# sparkfantutorial.net
KiCad netlist of a schematic drawn in EAGLE
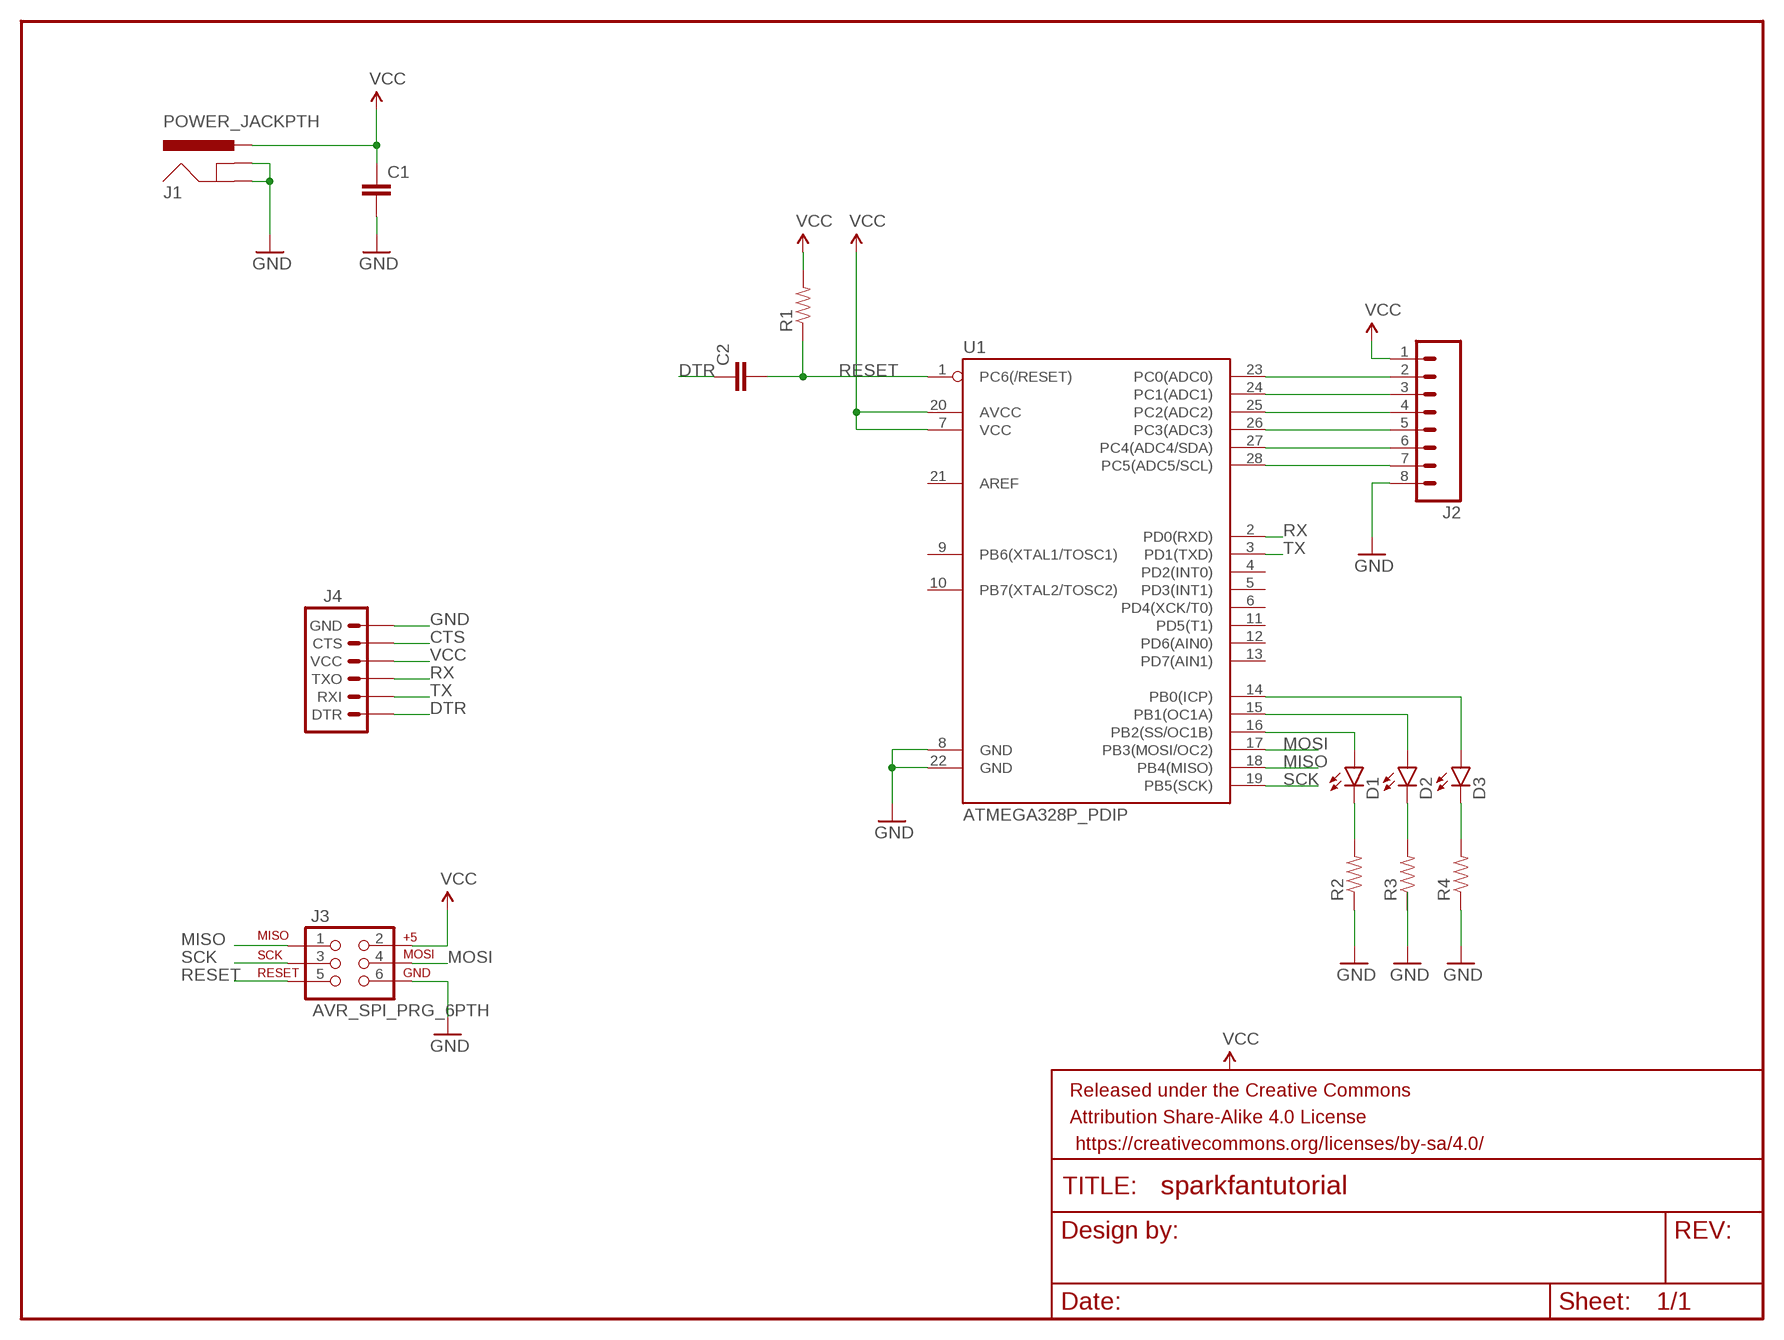
[diagram p0: schematic, sheet 1]

(export (version "E")
  (design (tool "Eeschema 10.0.6"))
  (components
    (comp (ref "C1")
      (value "CAPPTH")
      (footprint "eagle-import:CAP-PTH-SMALL")
      (libsource (lib "eagle-import") (part "CAPPTH"))
    )
    (comp (ref "C2")
      (value "CAPPTH")
      (footprint "eagle-import:CAP-PTH-SMALL")
      (libsource (lib "eagle-import") (part "CAPPTH"))
    )
    (comp (ref "D1")
      (value "LED5MM")
      (footprint "eagle-import:LED5MM")
      (libsource (lib "eagle-import") (part "LED5MM"))
    )
    (comp (ref "D2")
      (value "LED5MM")
      (footprint "eagle-import:LED5MM")
      (libsource (lib "eagle-import") (part "LED5MM"))
    )
    (comp (ref "D3")
      (value "LED5MM")
      (footprint "eagle-import:LED5MM")
      (libsource (lib "eagle-import") (part "LED5MM"))
    )
    (comp (ref "FRAME1")
      (value "FRAME-LETTER")
      (footprint "eagle-import:CREATIVE_COMMONS")
      (libsource (lib "eagle-import") (part "FRAME-LETTER"))
    )
    (comp (ref "J1")
      (value "POWER_JACKPTH")
      (footprint "eagle-import:POWER_JACK_PTH")
      (libsource (lib "eagle-import") (part "POWER_JACKPTH"))
    )
    (comp (ref "J2")
      (value "M08")
      (footprint "eagle-import:1X08_ROUND")
      (libsource (lib "eagle-import") (part "M08"))
    )
    (comp (ref "J3")
      (value "AVR_SPI_PRG_6PTH")
      (footprint "eagle-import:2X3")
      (libsource (lib "eagle-import") (part "AVR_SPI_PRG_6PTH"))
    )
    (comp (ref "J4")
      (value "ARDUINO_SERIAL_PROGRAMPTH")
      (footprint "eagle-import:1X06")
      (libsource (lib "eagle-import") (part "ARDUINO_SERIAL_PROGRAMPTH"))
    )
    (comp (ref "R1")
      (value "RESISTORPTH-1/4W")
      (footprint "eagle-import:AXIAL-0.4")
      (libsource (lib "eagle-import") (part "RESISTORPTH-1/4W"))
    )
    (comp (ref "R2")
      (value "RESISTORPTH-1/4W")
      (footprint "eagle-import:AXIAL-0.4")
      (libsource (lib "eagle-import") (part "RESISTORPTH-1/4W"))
    )
    (comp (ref "R3")
      (value "RESISTORPTH-1/4W")
      (footprint "eagle-import:AXIAL-0.4")
      (libsource (lib "eagle-import") (part "RESISTORPTH-1/4W"))
    )
    (comp (ref "R4")
      (value "RESISTORPTH-1/4W")
      (footprint "eagle-import:AXIAL-0.4")
      (libsource (lib "eagle-import") (part "RESISTORPTH-1/4W"))
    )
    (comp (ref "U1")
      (value "ATMEGA328P_PDIP")
      (footprint "eagle-import:DIL28-3")
      (libsource (lib "eagle-import") (part "ATMEGA328P_PDIP"))
    )
  )
  (nets
    (net (code "1") (name "/CTS") (class "Default")
      (node (ref "J4") (pin "5") (pinfunction "CTS_5") (pintype "passive"))
    )
    (net (code "2") (name "/DTR") (class "Default")
      (node (ref "C2") (pin "1") (pinfunction "1_1") (pintype "passive"))
      (node (ref "J4") (pin "1") (pinfunction "DTR_1") (pintype "passive"))
    )
    (net (code "3") (name "/MISO") (class "Default")
      (node (ref "J3") (pin "1") (pinfunction "1_1") (pintype "passive"))
      (node (ref "U1") (pin "18") (pinfunction "PB4(MISO)_18") (pintype "bidirectional"))
    )
    (net (code "4") (name "/MOSI") (class "Default")
      (node (ref "J3") (pin "4") (pinfunction "4_4") (pintype "passive"))
      (node (ref "U1") (pin "17") (pinfunction "PB3(MOSI/OC2)_17") (pintype "bidirectional"))
    )
    (net (code "5") (name "/RESET") (class "Default")
      (node (ref "C2") (pin "2") (pinfunction "2_2") (pintype "passive"))
      (node (ref "J3") (pin "5") (pinfunction "5_5") (pintype "passive"))
      (node (ref "R1") (pin "P$1") (pinfunction "1_P$1") (pintype "passive"))
      (node (ref "U1") (pin "1") (pinfunction "PC6(/RESET)_1") (pintype "bidirectional"))
    )
    (net (code "6") (name "/RX") (class "Default")
      (node (ref "J4") (pin "3") (pinfunction "TXO_3") (pintype "passive"))
      (node (ref "U1") (pin "2") (pinfunction "PD0(RXD)_2") (pintype "bidirectional"))
    )
    (net (code "7") (name "/SCK") (class "Default")
      (node (ref "J3") (pin "3") (pinfunction "3_3") (pintype "passive"))
      (node (ref "U1") (pin "19") (pinfunction "PB5(SCK)_19") (pintype "bidirectional"))
    )
    (net (code "8") (name "/TX") (class "Default")
      (node (ref "J4") (pin "2") (pinfunction "RXI_2") (pintype "passive"))
      (node (ref "U1") (pin "3") (pinfunction "PD1(TXD)_3") (pintype "bidirectional"))
    )
    (net (code "9") (name "GND") (class "Default")
      (node (ref "C1") (pin "2") (pinfunction "2_2") (pintype "passive"))
      (node (ref "J1") (pin "GND") (pinfunction "GND_GND") (pintype "bidirectional"))
      (node (ref "J1") (pin "GNDBREAK") (pinfunction "GNDBREAK_GNDBREAK") (pintype "bidirectional"))
      (node (ref "J2") (pin "8") (pinfunction "8_8") (pintype "passive"))
      (node (ref "J3") (pin "6") (pinfunction "6_6") (pintype "passive"))
      (node (ref "J4") (pin "6") (pinfunction "GND_6") (pintype "passive"))
      (node (ref "R2") (pin "P$1") (pinfunction "1_P$1") (pintype "passive"))
      (node (ref "R4") (pin "P$1") (pinfunction "1_P$1") (pintype "passive"))
      (node (ref "U1") (pin "22") (pinfunction "GND_22") (pintype "bidirectional"))
      (node (ref "U1") (pin "8") (pinfunction "GND_8") (pintype "bidirectional"))
    )
    (net (code "10") (name "Net-(D1-C)") (class "Default")
      (node (ref "D1") (pin "K") (pinfunction "C_K") (pintype "passive"))
      (node (ref "R2") (pin "P$2") (pinfunction "2_P$2") (pintype "passive"))
    )
    (net (code "11") (name "Net-(D2-C)") (class "Default")
      (node (ref "D2") (pin "K") (pinfunction "C_K") (pintype "passive"))
      (node (ref "R3") (pin "P$2") (pinfunction "2_P$2") (pintype "passive"))
    )
    (net (code "12") (name "Net-(D3-C)") (class "Default")
      (node (ref "D3") (pin "K") (pinfunction "C_K") (pintype "passive"))
      (node (ref "R4") (pin "P$2") (pinfunction "2_P$2") (pintype "passive"))
    )
    (net (code "13") (name "Net-(U1-PB0(ICP))") (class "Default")
      (node (ref "D3") (pin "A") (pinfunction "A_A") (pintype "passive"))
      (node (ref "U1") (pin "14") (pinfunction "PB0(ICP)_14") (pintype "bidirectional"))
    )
    (net (code "14") (name "Net-(U1-PB1(OC1A))") (class "Default")
      (node (ref "D2") (pin "A") (pinfunction "A_A") (pintype "passive"))
      (node (ref "U1") (pin "15") (pinfunction "PB1(OC1A)_15") (pintype "bidirectional"))
    )
    (net (code "15") (name "Net-(U1-PB2(SS{slash}OC1B))") (class "Default")
      (node (ref "D1") (pin "A") (pinfunction "A_A") (pintype "passive"))
      (node (ref "U1") (pin "16") (pinfunction "PB2(SS/OC1B)_16") (pintype "bidirectional"))
    )
    (net (code "16") (name "Net-(U1-PC0(ADC0))") (class "Default")
      (node (ref "J2") (pin "2") (pinfunction "2_2") (pintype "passive"))
      (node (ref "U1") (pin "23") (pinfunction "PC0(ADC0)_23") (pintype "bidirectional"))
    )
    (net (code "17") (name "Net-(U1-PC1(ADC1))") (class "Default")
      (node (ref "J2") (pin "3") (pinfunction "3_3") (pintype "passive"))
      (node (ref "U1") (pin "24") (pinfunction "PC1(ADC1)_24") (pintype "bidirectional"))
    )
    (net (code "18") (name "Net-(U1-PC2(ADC2))") (class "Default")
      (node (ref "J2") (pin "4") (pinfunction "4_4") (pintype "passive"))
      (node (ref "U1") (pin "25") (pinfunction "PC2(ADC2)_25") (pintype "bidirectional"))
    )
    (net (code "19") (name "Net-(U1-PC3(ADC3))") (class "Default")
      (node (ref "J2") (pin "5") (pinfunction "5_5") (pintype "passive"))
      (node (ref "U1") (pin "26") (pinfunction "PC3(ADC3)_26") (pintype "bidirectional"))
    )
    (net (code "20") (name "Net-(U1-PC4(ADC4{slash}SDA))") (class "Default")
      (node (ref "J2") (pin "6") (pinfunction "6_6") (pintype "passive"))
      (node (ref "U1") (pin "27") (pinfunction "PC4(ADC4/SDA)_27") (pintype "bidirectional"))
    )
    (net (code "21") (name "Net-(U1-PC5(ADC5{slash}SCL))") (class "Default")
      (node (ref "J2") (pin "7") (pinfunction "7_7") (pintype "passive"))
      (node (ref "U1") (pin "28") (pinfunction "PC5(ADC5/SCL)_28") (pintype "bidirectional"))
    )
    (net (code "22") (name "VCC") (class "Default")
      (node (ref "C1") (pin "1") (pinfunction "1_1") (pintype "passive"))
      (node (ref "J1") (pin "PWR") (pinfunction "PWR_PWR") (pintype "bidirectional"))
      (node (ref "J2") (pin "1") (pinfunction "1_1") (pintype "passive"))
      (node (ref "J3") (pin "2") (pinfunction "2_2") (pintype "passive"))
      (node (ref "J4") (pin "4") (pinfunction "VCC_4") (pintype "passive"))
      (node (ref "R1") (pin "P$2") (pinfunction "2_P$2") (pintype "passive"))
      (node (ref "U1") (pin "20") (pinfunction "AVCC_20") (pintype "bidirectional"))
      (node (ref "U1") (pin "7") (pinfunction "VCC_7") (pintype "bidirectional"))
    )
    (net (code "23") (name "unconnected-(R3-1-PadP$1)") (class "Default")
      (node (ref "R3") (pin "P$1") (pinfunction "1_P$1") (pintype "passive"))
    )
    (net (code "24") (name "unconnected-(U1-AREF-Pad21)") (class "Default")
      (node (ref "U1") (pin "21") (pinfunction "AREF_21") (pintype "bidirectional"))
    )
    (net (code "25") (name "unconnected-(U1-PB6(XTAL1{slash}TOSC1)-Pad9)") (class "Default")
      (node (ref "U1") (pin "9") (pinfunction "PB6(XTAL1/TOSC1)_9") (pintype "bidirectional"))
    )
    (net (code "26") (name "unconnected-(U1-PB7(XTAL2{slash}TOSC2)-Pad10)") (class "Default")
      (node (ref "U1") (pin "10") (pinfunction "PB7(XTAL2/TOSC2)_10") (pintype "bidirectional"))
    )
    (net (code "27") (name "unconnected-(U1-PD2(INT0)-Pad4)") (class "Default")
      (node (ref "U1") (pin "4") (pinfunction "PD2(INT0)_4") (pintype "bidirectional"))
    )
    (net (code "28") (name "unconnected-(U1-PD3(INT1)-Pad5)") (class "Default")
      (node (ref "U1") (pin "5") (pinfunction "PD3(INT1)_5") (pintype "bidirectional"))
    )
    (net (code "29") (name "unconnected-(U1-PD4(XCK{slash}T0)-Pad6)") (class "Default")
      (node (ref "U1") (pin "6") (pinfunction "PD4(XCK/T0)_6") (pintype "bidirectional"))
    )
    (net (code "30") (name "unconnected-(U1-PD5(T1)-Pad11)") (class "Default")
      (node (ref "U1") (pin "11") (pinfunction "PD5(T1)_11") (pintype "bidirectional"))
    )
    (net (code "31") (name "unconnected-(U1-PD6(AIN0)-Pad12)") (class "Default")
      (node (ref "U1") (pin "12") (pinfunction "PD6(AIN0)_12") (pintype "bidirectional"))
    )
    (net (code "32") (name "unconnected-(U1-PD7(AIN1)-Pad13)") (class "Default")
      (node (ref "U1") (pin "13") (pinfunction "PD7(AIN1)_13") (pintype "bidirectional"))
    )
  )
)
